# TIDA-01576_ADS8686S_ISO_Interface_Pg3-Po.net
KiCad netlist of a schematic drawn in Altium Designer
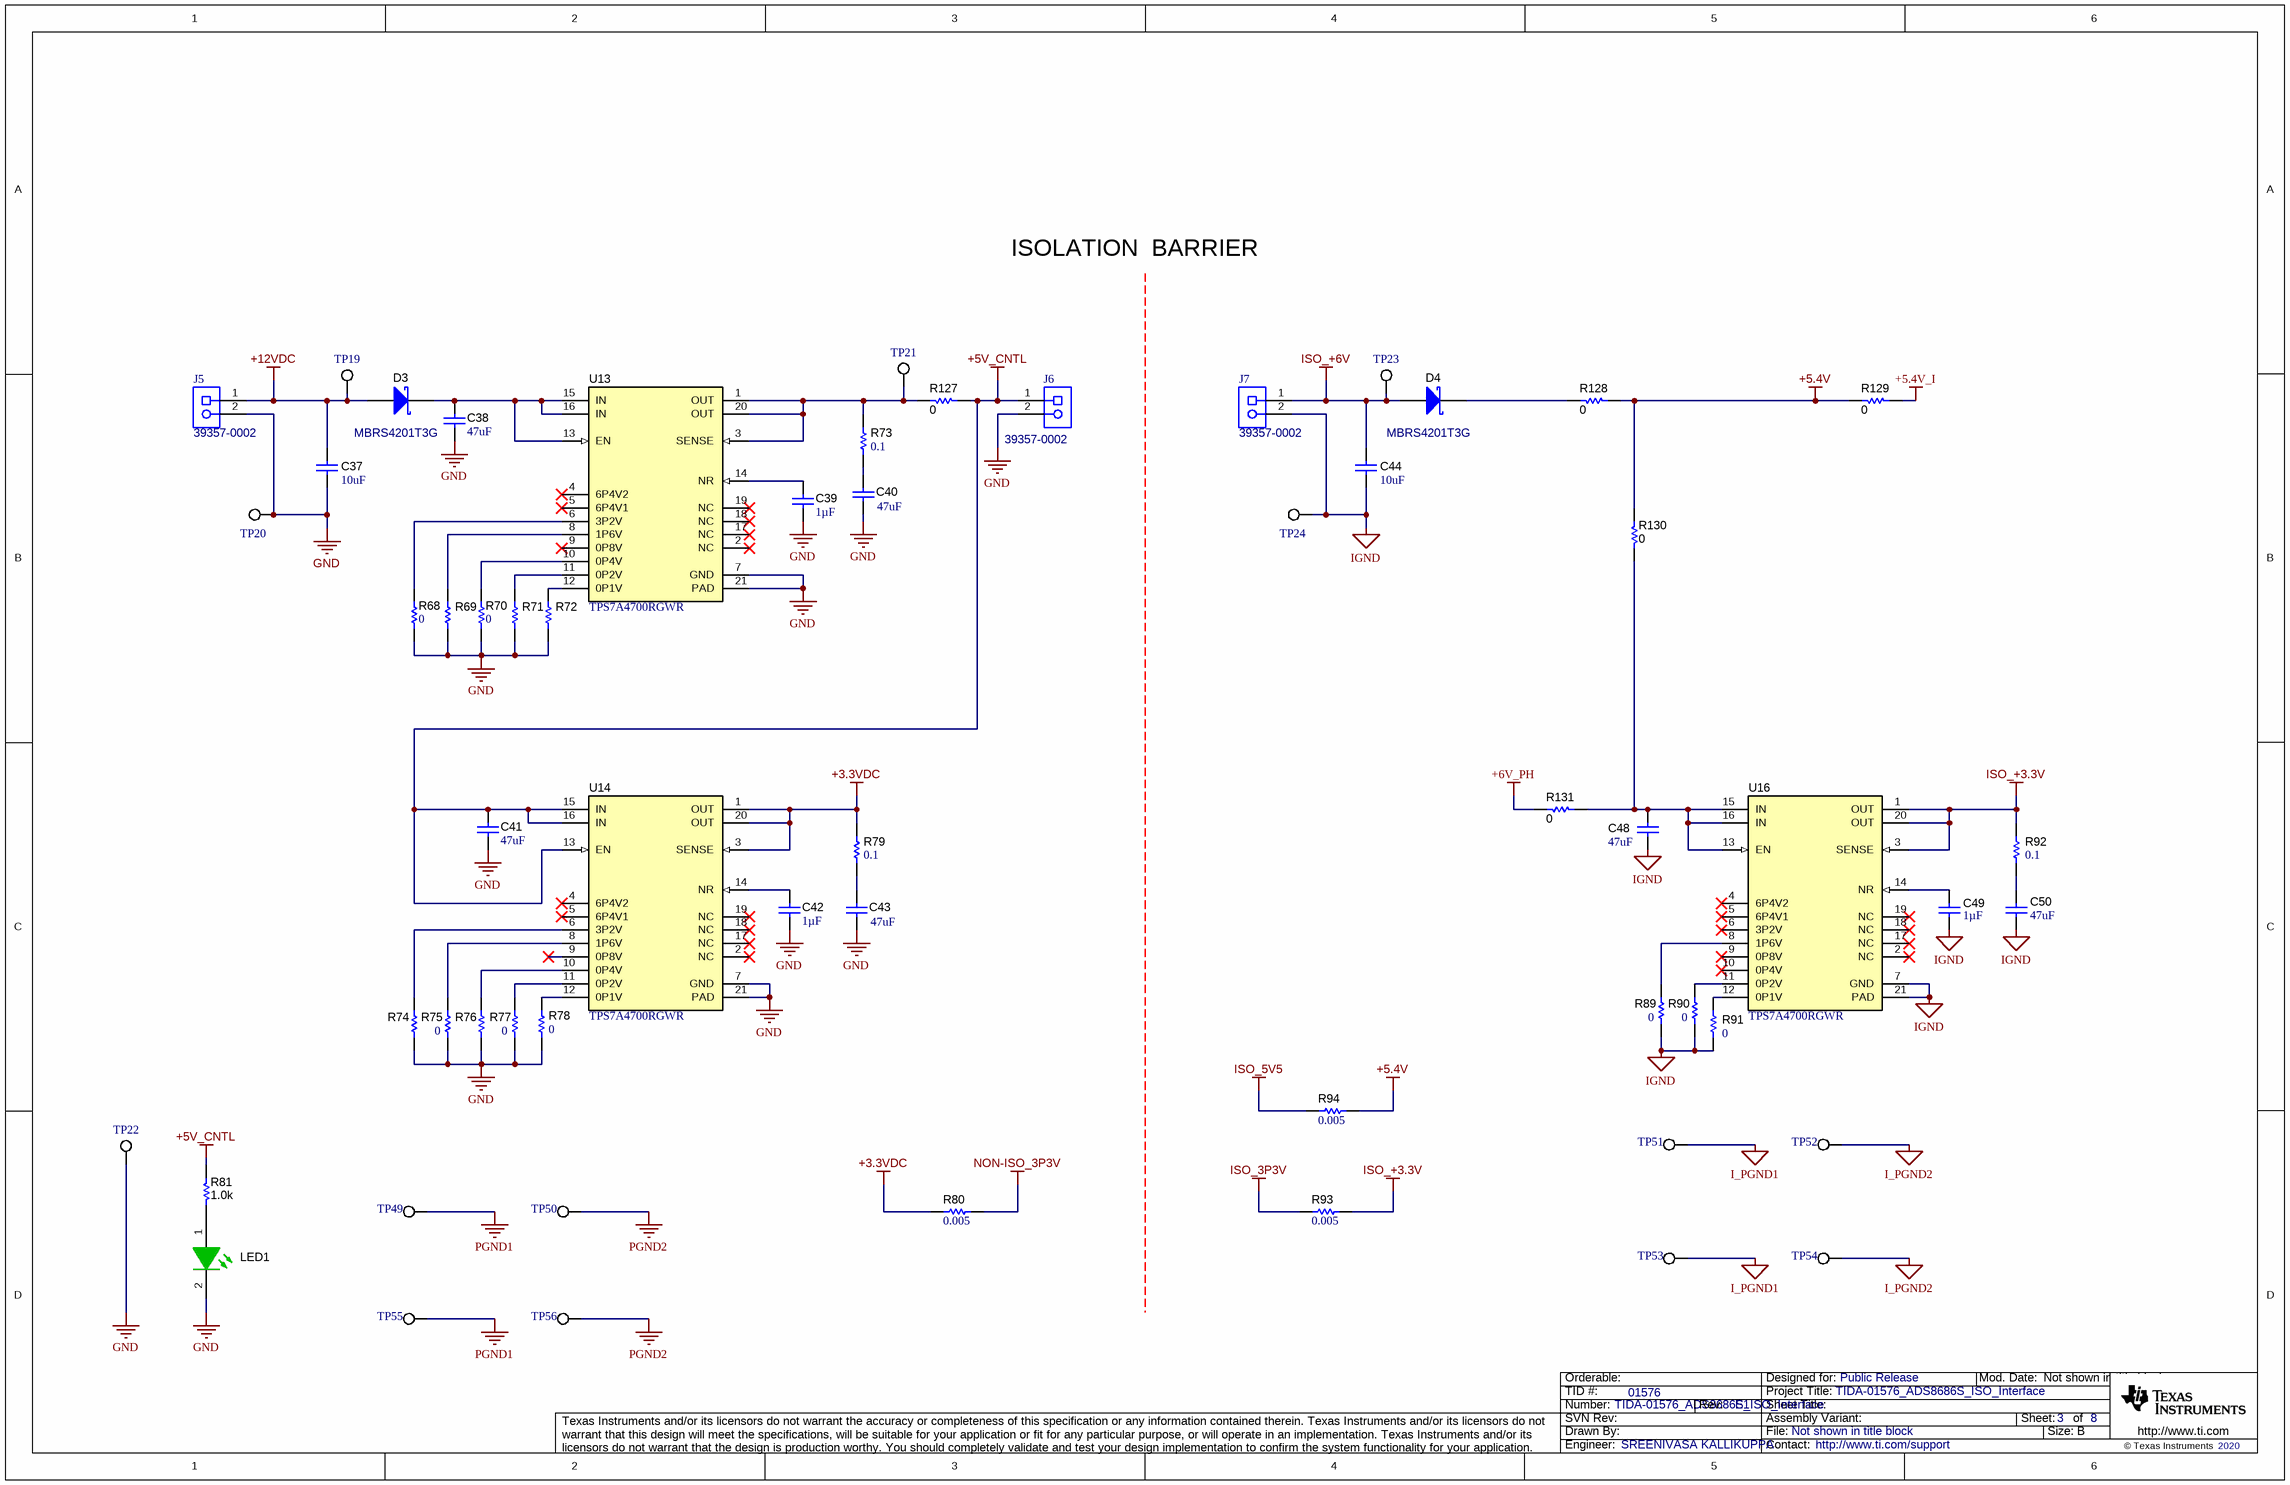
[diagram p0: TIDA-01576_ADS8686S_ISO_Interface_Pg3-PowerSupply.SchDoc]

(export (version "E")
  (design (tool "Eeschema 10.0.6"))
  (components
    (comp (ref "C37")
      (value "GRM32ER71H106KA12L")
      (footprint "1210_270")
      (description "CAP, CERM, 10 uF, 50 V, +/- 10%, X7R, 1210")
      (fields (field (name "MANUFACTURER") "MuRata") (field (name "VALUEDISPLAYED") "10uF"))
      (libsource (lib "Altium Vault - TI") (part "Capacitor"))
    )
    (comp (ref "C38")
      (value "C3216X5R1E476M160AC")
      (footprint "1206_190")
      (description "CAP, CERM, 47 uF, 25 V, +/- 20%, X5R, 1206_190")
      (fields
        (field (name "MANUFACTURER") "TDK")
        (field (name "VALUEDISPLAYED") "47uF")
        (field (name "PUBLISHER") "Texas Instruments")
      )
      (libsource (lib "Altium Vault - TI") (part "Capacitor"))
    )
    (comp (ref "C39")
      (value "C1608X7R1C105K080AC")
      (footprint "0603")
      (description "CAP, CERM, 1 uF, 16 V, +/- 10%, X7R, 0603")
      (fields
        (field (name "MANUFACTURER") "TDK")
        (field (name "CAP_F") "1µF")
        (field (name "PUBLISHER") "Texas Instruments")
      )
      (libsource (lib "Altium Vault - TI") (part "Capacitor"))
    )
    (comp (ref "C40")
      (value "C2012X5R1A476M125AC")
      (footprint "0805_HV")
      (description "CAP, CERM, 47 uF, 10 V, +/- 20%, X5R, 0805")
      (fields
        (field (name "MANUFACTURER") "TDK")
        (field (name "VALUEDISPLAYED") "47uF")
        (field (name "PUBLISHER") "Texas Instruments")
      )
      (libsource (lib "Altium Vault - TI") (part "Capacitor"))
    )
    (comp (ref "C41")
      (value "C3216X5R1E476M160AC")
      (footprint "1206_190")
      (description "CAP, CERM, 47 uF, 25 V, +/- 20%, X5R, 1206_190")
      (fields
        (field (name "MANUFACTURER") "TDK")
        (field (name "VALUEDISPLAYED") "47uF")
        (field (name "PUBLISHER") "Texas Instruments")
      )
      (libsource (lib "Altium Vault - TI") (part "Capacitor"))
    )
    (comp (ref "C42")
      (value "C1608X7R1C105K080AC")
      (footprint "0603")
      (description "CAP, CERM, 1 uF, 16 V, +/- 10%, X7R, 0603")
      (fields
        (field (name "MANUFACTURER") "TDK")
        (field (name "CAP_F") "1µF")
        (field (name "PUBLISHER") "Texas Instruments")
      )
      (libsource (lib "Altium Vault - TI") (part "Capacitor"))
    )
    (comp (ref "C43")
      (value "C2012X5R1A476M125AC")
      (footprint "0805_HV")
      (description "CAP, CERM, 47 uF, 10 V, +/- 20%, X5R, 0805")
      (fields
        (field (name "MANUFACTURER") "TDK")
        (field (name "VALUEDISPLAYED") "47uF")
        (field (name "PUBLISHER") "Texas Instruments")
      )
      (libsource (lib "Altium Vault - TI") (part "Capacitor"))
    )
    (comp (ref "C44")
      (value "GRM32ER71H106KA12L")
      (footprint "1210_270")
      (description "CAP, CERM, 10 uF, 50 V, +/- 10%, X7R, 1210")
      (fields (field (name "MANUFACTURER") "MuRata") (field (name "VALUEDISPLAYED") "10uF"))
      (libsource (lib "Altium Vault - TI") (part "Capacitor"))
    )
    (comp (ref "C48")
      (value "C3216X5R1E476M160AC")
      (footprint "1206_190")
      (description "CAP, CERM, 47 uF, 25 V, +/- 20%, X5R, 1206_190")
      (fields
        (field (name "MANUFACTURER") "TDK")
        (field (name "VALUEDISPLAYED") "47uF")
        (field (name "PUBLISHER") "Texas Instruments")
      )
      (libsource (lib "Altium Vault - TI") (part "Capacitor"))
    )
    (comp (ref "C49")
      (value "C1608X7R1C105K080AC")
      (footprint "0603")
      (description "CAP, CERM, 1 uF, 16 V, +/- 10%, X7R, 0603")
      (fields
        (field (name "MANUFACTURER") "TDK")
        (field (name "CAP_F") "1µF")
        (field (name "PUBLISHER") "Texas Instruments")
      )
      (libsource (lib "Altium Vault - TI") (part "Capacitor"))
    )
    (comp (ref "C50")
      (value "C2012X5R1A476M125AC")
      (footprint "0805_HV")
      (description "CAP, CERM, 47 uF, 10 V, +/- 20%, X5R, 0805")
      (fields
        (field (name "MANUFACTURER") "TDK")
        (field (name "VALUEDISPLAYED") "47uF")
        (field (name "PUBLISHER") "Texas Instruments")
      )
      (libsource (lib "Altium Vault - TI") (part "Capacitor"))
    )
    (comp (ref "D3")
      (value "MBRS4201T3G")
      (footprint "SMC")
      (description "Diode, Schottky, 200 V, 4 A, SMC")
      (fields (field (name "MANUFACTURER") "ON Semiconductor") (field (name "PUBLISHER") "Texas Instruments"))
      (libsource (lib "Altium Vault - TI") (part "DIODE_SCHOTTKY"))
    )
    (comp (ref "D4")
      (value "MBRS4201T3G")
      (footprint "SMC")
      (description "Diode, Schottky, 200 V, 4 A, SMC")
      (fields (field (name "MANUFACTURER") "ON Semiconductor") (field (name "PUBLISHER") "Texas Instruments"))
      (libsource (lib "Altium Vault - TI") (part "DIODE_SCHOTTKY"))
    )
    (comp (ref "J5")
      (value "39357-0002")
      (footprint "MOLEX_39357-0002")
      (description "Terminal Block, 3.5 mm, 2x1, Tin, TH")
      (fields (field (name "MANUFACTURER") "Molex") (field (name "PUBLISHER") "Texas Instruments"))
      (libsource (lib "Altium Vault - TI") (part "Receptacle_2x1"))
    )
    (comp (ref "J6")
      (value "39357-0002")
      (footprint "MOLEX_39357-0002")
      (description "Terminal Block, 3.5 mm, 2x1, Tin, TH")
      (fields (field (name "MANUFACTURER") "Molex") (field (name "PUBLISHER") "Texas Instruments"))
      (libsource (lib "") (part "Receptacle_2x1_1"))
    )
    (comp (ref "J7")
      (value "39357-0002")
      (footprint "MOLEX_39357-0002")
      (description "Terminal Block, 3.5 mm, 2x1, Tin, TH")
      (fields (field (name "MANUFACTURER") "Molex") (field (name "PUBLISHER") "Texas Instruments"))
      (libsource (lib "Altium Vault - TI") (part "Receptacle_2x1"))
    )
    (comp (ref "LED1")
      (value "LTST-C193TGKT-5A")
      (footprint "LTST-C193_Green_S")
      (description "LED, Green, SMD")
      (fields (field (name "MANUFACTURER") "Lite-On"))
      (libsource (lib "Altium Vault - TI") (part "LED_Green_A1K2"))
    )
    (comp (ref "R68")
      (value "CRCW06030000Z0EA")
      (footprint "0603")
      (description "RES, 0, 5%, 0.1 W, 0603")
      (fields
        (field (name "MANUFACTURER") "Vishay-Dale")
        (field (name "VALUEDISPLAYED") "0")
        (field (name "PUBLISHER") "Texas Instruments")
      )
      (libsource (lib "Altium Vault - TI") (part "Resistor"))
    )
    (comp (ref "R69")
      (value "CRCW06030000Z0EA")
      (footprint "0603")
      (description "RES, 0, 5%, 0.1 W, 0603")
      (fields (field (name "MANUFACTURER") "Vishay-Dale") (field (name "PUBLISHER") "Texas Instruments"))
      (libsource (lib "Altium Vault - TI") (part "Resistor"))
    )
    (comp (ref "R70")
      (value "CRCW06030000Z0EA")
      (footprint "0603")
      (description "RES, 0, 5%, 0.1 W, 0603")
      (fields
        (field (name "MANUFACTURER") "Vishay-Dale")
        (field (name "VALUEDISPLAYED") "0")
        (field (name "PUBLISHER") "Texas Instruments")
      )
      (libsource (lib "Altium Vault - TI") (part "Resistor"))
    )
    (comp (ref "R71")
      (value "CRCW06030000Z0EA")
      (footprint "0603")
      (description "RES, 0, 5%, 0.1 W, 0603")
      (fields (field (name "MANUFACTURER") "Vishay-Dale") (field (name "PUBLISHER") "Texas Instruments"))
      (libsource (lib "Altium Vault - TI") (part "Resistor"))
    )
    (comp (ref "R72")
      (value "CRCW06030000Z0EA")
      (footprint "0603")
      (description "RES, 0, 5%, 0.1 W, 0603")
      (fields (field (name "MANUFACTURER") "Vishay-Dale") (field (name "PUBLISHER") "Texas Instruments"))
      (libsource (lib "Altium Vault - TI") (part "Resistor"))
    )
    (comp (ref "R73")
      (value "ERJ-3RSFR10V")
      (footprint "0603")
      (description "RES, 0.1, 1%, 0.1 W, 0603")
      (fields
        (field (name "MANUFACTURER") "Panasonic")
        (field (name "VALUEDISPLAYED") "0.1")
        (field (name "PUBLISHER") "Texas Instruments")
      )
      (libsource (lib "Altium Vault - TI") (part "Resistor"))
    )
    (comp (ref "R74")
      (value "CRCW06030000Z0EA")
      (footprint "0603")
      (description "RES, 0, 5%, 0.1 W, 0603")
      (fields (field (name "MANUFACTURER") "Vishay-Dale") (field (name "PUBLISHER") "Texas Instruments"))
      (libsource (lib "Altium Vault - TI") (part "Resistor"))
    )
    (comp (ref "R75")
      (value "CRCW06030000Z0EA")
      (footprint "0603")
      (description "RES, 0, 5%, 0.1 W, 0603")
      (fields
        (field (name "MANUFACTURER") "Vishay-Dale")
        (field (name "VALUEDISPLAYED") "0")
        (field (name "PUBLISHER") "Texas Instruments")
      )
      (libsource (lib "Altium Vault - TI") (part "Resistor"))
    )
    (comp (ref "R76")
      (value "CRCW06030000Z0EA")
      (footprint "0603")
      (description "RES, 0, 5%, 0.1 W, 0603")
      (fields (field (name "MANUFACTURER") "Vishay-Dale") (field (name "PUBLISHER") "Texas Instruments"))
      (libsource (lib "Altium Vault - TI") (part "Resistor"))
    )
    (comp (ref "R77")
      (value "CRCW06030000Z0EA")
      (footprint "0603")
      (description "RES, 0, 5%, 0.1 W, 0603")
      (fields
        (field (name "MANUFACTURER") "Vishay-Dale")
        (field (name "VALUEDISPLAYED") "0")
        (field (name "PUBLISHER") "Texas Instruments")
      )
      (libsource (lib "Altium Vault - TI") (part "Resistor"))
    )
    (comp (ref "R78")
      (value "CRCW06030000Z0EA")
      (footprint "0603")
      (description "RES, 0, 5%, 0.1 W, 0603")
      (fields
        (field (name "MANUFACTURER") "Vishay-Dale")
        (field (name "VALUEDISPLAYED") "0")
        (field (name "PUBLISHER") "Texas Instruments")
      )
      (libsource (lib "Altium Vault - TI") (part "Resistor"))
    )
    (comp (ref "R79")
      (value "ERJ-3RSFR10V")
      (footprint "0603")
      (description "RES, 0.1, 1%, 0.1 W, 0603")
      (fields
        (field (name "MANUFACTURER") "Panasonic")
        (field (name "VALUEDISPLAYED") "0.1")
        (field (name "PUBLISHER") "Texas Instruments")
      )
      (libsource (lib "Altium Vault - TI") (part "Resistor"))
    )
    (comp (ref "R80")
      (value "ERJ6LWFR005V")
      (footprint "0805_HV")
      (description "RES, 0.005, 1%, 0.5 W, AEC-Q200 Grade 1, 0805")
      (fields (field (name "MANUFACTURER") "Panasonic") (field (name "VALUEDISPLAYED") "0.005"))
      (libsource (lib "Altium Vault - TI") (part "Resistor"))
    )
    (comp (ref "R81")
      (value "RC0603JR-071KL")
      (footprint "0603")
      (description "RES, 1.0 k, 5%, 0.1 W, 0603")
      (fields
        (field (name "VALUEDISPLAYED") "1.0k")
        (field (name "MANUFACTURER") "Yageo America")
        (field (name "PUBLISHER") "Texas Instruments")
      )
      (libsource (lib "Resistor_0603") (part "RC0603JR-071KL"))
    )
    (comp (ref "R89")
      (value "CRCW06030000Z0EA")
      (footprint "0603")
      (description "RES, 0, 5%, 0.1 W, 0603")
      (fields
        (field (name "MANUFACTURER") "Vishay-Dale")
        (field (name "VALUEDISPLAYED") "0")
        (field (name "PUBLISHER") "Texas Instruments")
      )
      (libsource (lib "Altium Vault - TI") (part "Resistor"))
    )
    (comp (ref "R90")
      (value "CRCW06030000Z0EA")
      (footprint "0603")
      (description "RES, 0, 5%, 0.1 W, 0603")
      (fields
        (field (name "MANUFACTURER") "Vishay-Dale")
        (field (name "VALUEDISPLAYED") "0")
        (field (name "PUBLISHER") "Texas Instruments")
      )
      (libsource (lib "Altium Vault - TI") (part "Resistor"))
    )
    (comp (ref "R91")
      (value "CRCW06030000Z0EA")
      (footprint "0603")
      (description "RES, 0, 5%, 0.1 W, 0603")
      (fields
        (field (name "MANUFACTURER") "Vishay-Dale")
        (field (name "VALUEDISPLAYED") "0")
        (field (name "PUBLISHER") "Texas Instruments")
      )
      (libsource (lib "Altium Vault - TI") (part "Resistor"))
    )
    (comp (ref "R92")
      (value "ERJ-3RSFR10V")
      (footprint "0603")
      (description "RES, 0.1, 1%, 0.1 W, 0603")
      (fields
        (field (name "MANUFACTURER") "Panasonic")
        (field (name "VALUEDISPLAYED") "0.1")
        (field (name "PUBLISHER") "Texas Instruments")
      )
      (libsource (lib "Altium Vault - TI") (part "Resistor"))
    )
    (comp (ref "R93")
      (value "ERJ6LWFR005V")
      (footprint "0805_HV")
      (description "RES, 0.005, 1%, 0.5 W, AEC-Q200 Grade 1, 0805")
      (fields (field (name "MANUFACTURER") "Panasonic") (field (name "VALUEDISPLAYED") "0.005"))
      (libsource (lib "Altium Vault - TI") (part "Resistor"))
    )
    (comp (ref "R94")
      (value "ERJ6LWFR005V")
      (footprint "0805_HV")
      (description "RES, 0.005, 1%, 0.5 W, AEC-Q200 Grade 1, 0805")
      (fields (field (name "MANUFACTURER") "Panasonic") (field (name "VALUEDISPLAYED") "0.005"))
      (libsource (lib "Altium Vault - TI") (part "Resistor"))
    )
    (comp (ref "R127")
      (value "CRCW06030000Z0EA")
      (footprint "0603")
      (description "RES, 0, 5%, 0.1 W, 0603")
      (fields
        (field (name "VALUEDISPLAYED") "0")
        (field (name "MANUFACTURER") "Vishay-Dale")
        (field (name "PUBLISHER") "Texas Instruments")
      )
      (libsource (lib "Resistor_0603") (part "CRCW06030000Z0EA"))
    )
    (comp (ref "R128")
      (value "CRCW06030000Z0EA")
      (footprint "0603")
      (description "RES, 0, 5%, 0.1 W, 0603")
      (fields
        (field (name "VALUEDISPLAYED") "0")
        (field (name "MANUFACTURER") "Vishay-Dale")
        (field (name "PUBLISHER") "Texas Instruments")
      )
      (libsource (lib "Resistor_0603") (part "CRCW06030000Z0EA"))
    )
    (comp (ref "R129")
      (value "CRCW06030000Z0EA")
      (footprint "0603")
      (description "RES, 0, 5%, 0.1 W, 0603")
      (fields
        (field (name "VALUEDISPLAYED") "0")
        (field (name "MANUFACTURER") "Vishay-Dale")
        (field (name "PUBLISHER") "Texas Instruments")
      )
      (libsource (lib "Resistor_0603") (part "CRCW06030000Z0EA"))
    )
    (comp (ref "R130")
      (value "CRCW06030000Z0EA")
      (footprint "0603")
      (description "RES, 0, 5%, 0.1 W, 0603")
      (fields
        (field (name "VALUEDISPLAYED") "0")
        (field (name "MANUFACTURER") "Vishay-Dale")
        (field (name "PUBLISHER") "Texas Instruments")
      )
      (libsource (lib "Resistor_0603") (part "CRCW06030000Z0EA"))
    )
    (comp (ref "R131")
      (value "CRCW06030000Z0EA")
      (footprint "0603")
      (description "RES, 0, 5%, 0.1 W, 0603")
      (fields
        (field (name "VALUEDISPLAYED") "0")
        (field (name "MANUFACTURER") "Vishay-Dale")
        (field (name "PUBLISHER") "Texas Instruments")
      )
      (libsource (lib "Resistor_0603") (part "CRCW06030000Z0EA"))
    )
    (comp (ref "TP19")
      (value "5015")
      (footprint "Testpoint_Keystone_Miniature")
      (description "Test Point, Miniature, SMT")
      (fields (field (name "MANUFACTURER") "Keystone") (field (name "PUBLISHER") "Texas Instruments"))
      (libsource (lib "Altium Vault - TI") (part "5015"))
    )
    (comp (ref "TP20")
      (value "5015")
      (footprint "Testpoint_Keystone_Miniature")
      (description "Test Point, Miniature, SMT")
      (fields (field (name "MANUFACTURER") "Keystone") (field (name "PUBLISHER") "Texas Instruments"))
      (libsource (lib "Altium Vault - TI") (part "5015"))
    )
    (comp (ref "TP21")
      (value "5015")
      (footprint "Testpoint_Keystone_Miniature")
      (description "Test Point, Miniature, SMT")
      (fields (field (name "MANUFACTURER") "Keystone") (field (name "PUBLISHER") "Texas Instruments"))
      (libsource (lib "Altium Vault - TI") (part "5015"))
    )
    (comp (ref "TP22")
      (value "5015")
      (footprint "Testpoint_Keystone_Miniature")
      (description "Test Point, Miniature, SMT")
      (fields (field (name "MANUFACTURER") "Keystone") (field (name "PUBLISHER") "Texas Instruments"))
      (libsource (lib "Altium Vault - TI") (part "5015"))
    )
    (comp (ref "TP23")
      (value "5015")
      (footprint "Testpoint_Keystone_Miniature")
      (description "Test Point, Miniature, SMT")
      (fields (field (name "MANUFACTURER") "Keystone") (field (name "PUBLISHER") "Texas Instruments"))
      (libsource (lib "Altium Vault - TI") (part "5015"))
    )
    (comp (ref "TP24")
      (value "5015")
      (footprint "Testpoint_Keystone_Miniature")
      (description "Test Point, Miniature, SMT")
      (fields (field (name "MANUFACTURER") "Keystone") (field (name "PUBLISHER") "Texas Instruments"))
      (libsource (lib "Altium Vault - TI") (part "5015"))
    )
    (comp (ref "TP49")
      (value "5015")
      (footprint "Testpoint_Keystone_Miniature")
      (description "Test Point, Miniature, SMT")
      (fields (field (name "MANUFACTURER") "Keystone") (field (name "PUBLISHER") "Texas Instruments"))
      (libsource (lib "Altium Vault - TI") (part "5015"))
    )
    (comp (ref "TP50")
      (value "5015")
      (footprint "Testpoint_Keystone_Miniature")
      (description "Test Point, Miniature, SMT")
      (fields (field (name "MANUFACTURER") "Keystone") (field (name "PUBLISHER") "Texas Instruments"))
      (libsource (lib "Altium Vault - TI") (part "5015"))
    )
    (comp (ref "TP51")
      (value "5015")
      (footprint "Testpoint_Keystone_Miniature")
      (description "Test Point, Miniature, SMT")
      (fields (field (name "MANUFACTURER") "Keystone") (field (name "PUBLISHER") "Texas Instruments"))
      (libsource (lib "Altium Vault - TI") (part "5015"))
    )
    (comp (ref "TP52")
      (value "5015")
      (footprint "Testpoint_Keystone_Miniature")
      (description "Test Point, Miniature, SMT")
      (fields (field (name "MANUFACTURER") "Keystone") (field (name "PUBLISHER") "Texas Instruments"))
      (libsource (lib "Altium Vault - TI") (part "5015"))
    )
    (comp (ref "TP53")
      (value "5015")
      (footprint "Testpoint_Keystone_Miniature")
      (description "Test Point, Miniature, SMT")
      (fields (field (name "MANUFACTURER") "Keystone") (field (name "PUBLISHER") "Texas Instruments"))
      (libsource (lib "Altium Vault - TI") (part "5015"))
    )
    (comp (ref "TP54")
      (value "5015")
      (footprint "Testpoint_Keystone_Miniature")
      (description "Test Point, Miniature, SMT")
      (fields (field (name "MANUFACTURER") "Keystone") (field (name "PUBLISHER") "Texas Instruments"))
      (libsource (lib "Altium Vault - TI") (part "5015"))
    )
    (comp (ref "TP55")
      (value "5015")
      (footprint "Testpoint_Keystone_Miniature")
      (description "Test Point, Miniature, SMT")
      (fields (field (name "MANUFACTURER") "Keystone") (field (name "PUBLISHER") "Texas Instruments"))
      (libsource (lib "Altium Vault - TI") (part "5015"))
    )
    (comp (ref "TP56")
      (value "5015")
      (footprint "Testpoint_Keystone_Miniature")
      (description "Test Point, Miniature, SMT")
      (fields (field (name "MANUFACTURER") "Keystone") (field (name "PUBLISHER") "Texas Instruments"))
      (libsource (lib "Altium Vault - TI") (part "5015"))
    )
    (comp (ref "U13")
      (value "TPS7A4700RGWR")
      (footprint "RGW0020A")
      (description "36-V, 1-A, 4.17-uVRMS, RF LDO Voltage Regulator, RGW0020A (VQFN-20)")
      (fields
        (field (name "ALTERNATE PARTNUMBER") "TPS7A4700RGWT")
        (field (name "MANUFACTURER") "Texas Instruments")
        (field (name "PARTNUMBER") "TPS7A4700RGWR")
        (field (name "PUBLISHER") "Texas Instruments")
      )
      (libsource (lib "Altium Vault - TI") (part "TPS7A4700RGW"))
    )
    (comp (ref "U14")
      (value "TPS7A4700RGWR")
      (footprint "RGW0020A")
      (description "36-V, 1-A, 4.17-uVRMS, RF LDO Voltage Regulator, RGW0020A (VQFN-20)")
      (fields
        (field (name "ALTERNATE PARTNUMBER") "TPS7A4700RGWT")
        (field (name "MANUFACTURER") "Texas Instruments")
        (field (name "PARTNUMBER") "TPS7A4700RGWR")
        (field (name "PUBLISHER") "Texas Instruments")
      )
      (libsource (lib "Altium Vault - TI") (part "TPS7A4700RGW"))
    )
    (comp (ref "U16")
      (value "TPS7A4700RGWR")
      (footprint "RGW0020A")
      (description "36-V, 1-A, 4.17-uVRMS, RF LDO Voltage Regulator, RGW0020A (VQFN-20)")
      (fields
        (field (name "ALTERNATE PARTNUMBER") "TPS7A4700RGWT")
        (field (name "MANUFACTURER") "Texas Instruments")
        (field (name "PARTNUMBER") "TPS7A4700RGWR")
        (field (name "PUBLISHER") "Texas Instruments")
      )
      (libsource (lib "Altium Vault - TI") (part "TPS7A4700RGW"))
    )
  )
  (nets
    (net (code "1") (name "+3.3VDC") (class "Default")
      (node (ref "R79") (pin "2") (pinfunction "2_2") (pintype "passive"))
      (node (ref "R80") (pin "2") (pinfunction "2_2") (pintype "passive"))
      (node (ref "U14") (pin "1") (pinfunction "OUT_1") (pintype "power_in"))
      (node (ref "U14") (pin "20") (pinfunction "OUT_20") (pintype "power_in"))
      (node (ref "U14") (pin "3") (pinfunction "SENSE_3") (pintype "input"))
    )
    (net (code "2") (name "+5.4V") (class "Default")
      (node (ref "R128") (pin "1") (pinfunction "1_1") (pintype "passive"))
      (node (ref "R129") (pin "2") (pinfunction "2_2") (pintype "passive"))
      (node (ref "R130") (pin "1") (pinfunction "1_1") (pintype "passive"))
      (node (ref "R94") (pin "2") (pinfunction "2_2") (pintype "passive"))
    )
    (net (code "3") (name "+5.4V_I") (class "Default")
      (node (ref "R129") (pin "1") (pinfunction "1_1") (pintype "passive"))
    )
    (net (code "4") (name "+5V_CNTL") (class "Default")
      (node (ref "C41") (pin "1") (pinfunction "1_1") (pintype "passive"))
      (node (ref "J6") (pin "1") (pinfunction "1_1") (pintype "passive"))
      (node (ref "R127") (pin "1") (pinfunction "1_1") (pintype "passive"))
      (node (ref "R81") (pin "2") (pinfunction "2_2") (pintype "passive"))
      (node (ref "U14") (pin "13") (pinfunction "EN_13") (pintype "input"))
      (node (ref "U14") (pin "15") (pinfunction "IN_15") (pintype "power_in"))
      (node (ref "U14") (pin "16") (pinfunction "IN_16") (pintype "power_in"))
    )
    (net (code "5") (name "+6V_PH") (class "Default")
      (node (ref "R131") (pin "1") (pinfunction "1_1") (pintype "passive"))
    )
    (net (code "6") (name "+12VDC") (class "Default")
      (node (ref "C37") (pin "1") (pinfunction "1_1") (pintype "passive"))
      (node (ref "D3") (pin "2") (pinfunction "A_2") (pintype "passive"))
      (node (ref "J5") (pin "1") (pinfunction "1_1") (pintype "passive"))
      (node (ref "TP19") (pin "1") (pintype "passive"))
    )
    (net (code "7") (name "GND") (class "Default")
      (node (ref "C37") (pin "2") (pinfunction "2_2") (pintype "passive"))
      (node (ref "C38") (pin "2") (pinfunction "2_2") (pintype "passive"))
      (node (ref "C39") (pin "2") (pinfunction "2_2") (pintype "passive"))
      (node (ref "C40") (pin "2") (pinfunction "2_2") (pintype "passive"))
      (node (ref "C41") (pin "2") (pinfunction "2_2") (pintype "passive"))
      (node (ref "C42") (pin "2") (pinfunction "2_2") (pintype "passive"))
      (node (ref "C43") (pin "2") (pinfunction "2_2") (pintype "passive"))
      (node (ref "J5") (pin "2") (pinfunction "2_2") (pintype "passive"))
      (node (ref "J6") (pin "2") (pinfunction "2_2") (pintype "passive"))
      (node (ref "LED1") (pin "2") (pinfunction "K_2") (pintype "passive"))
      (node (ref "R68") (pin "1") (pinfunction "1_1") (pintype "passive"))
      (node (ref "R69") (pin "1") (pinfunction "1_1") (pintype "passive"))
      (node (ref "R70") (pin "1") (pinfunction "1_1") (pintype "passive"))
      (node (ref "R71") (pin "1") (pinfunction "1_1") (pintype "passive"))
      (node (ref "R72") (pin "1") (pinfunction "1_1") (pintype "passive"))
      (node (ref "R74") (pin "1") (pinfunction "1_1") (pintype "passive"))
      (node (ref "R75") (pin "1") (pinfunction "1_1") (pintype "passive"))
      (node (ref "R76") (pin "1") (pinfunction "1_1") (pintype "passive"))
      (node (ref "R77") (pin "1") (pinfunction "1_1") (pintype "passive"))
      (node (ref "R78") (pin "1") (pinfunction "1_1") (pintype "passive"))
      (node (ref "TP20") (pin "1") (pintype "passive"))
      (node (ref "TP22") (pin "1") (pintype "passive"))
      (node (ref "U13") (pin "21") (pinfunction "PAD_21") (pintype "passive"))
      (node (ref "U13") (pin "7") (pinfunction "GND_7") (pintype "power_in"))
      (node (ref "U14") (pin "21") (pinfunction "PAD_21") (pintype "passive"))
      (node (ref "U14") (pin "7") (pinfunction "GND_7") (pintype "power_in"))
    )
    (net (code "8") (name "IGND") (class "Default")
      (node (ref "C44") (pin "2") (pinfunction "2_2") (pintype "passive"))
      (node (ref "C48") (pin "2") (pinfunction "2_2") (pintype "passive"))
      (node (ref "C49") (pin "2") (pinfunction "2_2") (pintype "passive"))
      (node (ref "C50") (pin "2") (pinfunction "2_2") (pintype "passive"))
      (node (ref "J7") (pin "2") (pinfunction "2_2") (pintype "passive"))
      (node (ref "R89") (pin "1") (pinfunction "1_1") (pintype "passive"))
      (node (ref "R90") (pin "1") (pinfunction "1_1") (pintype "passive"))
      (node (ref "R91") (pin "1") (pinfunction "1_1") (pintype "passive"))
      (node (ref "TP24") (pin "1") (pintype "passive"))
      (node (ref "U16") (pin "21") (pinfunction "PAD_21") (pintype "passive"))
      (node (ref "U16") (pin "7") (pinfunction "GND_7") (pintype "power_in"))
    )
    (net (code "9") (name "ISO_+3.3V") (class "Default")
      (node (ref "R92") (pin "2") (pinfunction "2_2") (pintype "passive"))
      (node (ref "R93") (pin "2") (pinfunction "2_2") (pintype "passive"))
      (node (ref "U16") (pin "1") (pinfunction "OUT_1") (pintype "power_in"))
      (node (ref "U16") (pin "20") (pinfunction "OUT_20") (pintype "power_in"))
      (node (ref "U16") (pin "3") (pinfunction "SENSE_3") (pintype "input"))
    )
    (net (code "10") (name "ISO_+6V") (class "Default")
      (node (ref "C44") (pin "1") (pinfunction "1_1") (pintype "passive"))
      (node (ref "D4") (pin "2") (pinfunction "A_2") (pintype "passive"))
      (node (ref "J7") (pin "1") (pinfunction "1_1") (pintype "passive"))
      (node (ref "TP23") (pin "1") (pintype "passive"))
    )
    (net (code "11") (name "ISO_3P3V") (class "Default")
      (node (ref "R93") (pin "1") (pinfunction "1_1") (pintype "passive"))
    )
    (net (code "12") (name "ISO_5V5") (class "Default")
      (node (ref "R94") (pin "1") (pinfunction "1_1") (pintype "passive"))
    )
    (net (code "13") (name "I_PGND1") (class "Default")
      (node (ref "TP51") (pin "1") (pintype "passive"))
      (node (ref "TP53") (pin "1") (pintype "passive"))
    )
    (net (code "14") (name "I_PGND2") (class "Default")
      (node (ref "TP52") (pin "1") (pintype "passive"))
      (node (ref "TP54") (pin "1") (pintype "passive"))
    )
    (net (code "15") (name "NON-ISO_3P3V") (class "Default")
      (node (ref "R80") (pin "1") (pinfunction "1_1") (pintype "passive"))
    )
    (net (code "16") (name "Net-(C40-Pad1)") (class "Default")
      (node (ref "C40") (pin "1") (pinfunction "1_1") (pintype "passive"))
      (node (ref "R73") (pin "1") (pinfunction "1_1") (pintype "passive"))
    )
    (net (code "17") (name "Net-(C43-Pad1)") (class "Default")
      (node (ref "C43") (pin "1") (pinfunction "1_1") (pintype "passive"))
      (node (ref "R79") (pin "1") (pinfunction "1_1") (pintype "passive"))
    )
    (net (code "18") (name "Net-(C50-Pad1)") (class "Default")
      (node (ref "C50") (pin "1") (pinfunction "1_1") (pintype "passive"))
      (node (ref "R92") (pin "1") (pinfunction "1_1") (pintype "passive"))
    )
    (net (code "19") (name "Net-(D3-K)") (class "Default")
      (node (ref "C38") (pin "1") (pinfunction "1_1") (pintype "passive"))
      (node (ref "D3") (pin "1") (pinfunction "K_1") (pintype "passive"))
      (node (ref "U13") (pin "13") (pinfunction "EN_13") (pintype "input"))
      (node (ref "U13") (pin "15") (pinfunction "IN_15") (pintype "power_in"))
      (node (ref "U13") (pin "16") (pinfunction "IN_16") (pintype "power_in"))
    )
    (net (code "20") (name "Net-(D4-K)") (class "Default")
      (node (ref "D4") (pin "1") (pinfunction "K_1") (pintype "passive"))
      (node (ref "R128") (pin "2") (pinfunction "2_2") (pintype "passive"))
    )
    (net (code "21") (name "Net-(LED1-A)") (class "Default")
      (node (ref "LED1") (pin "1") (pinfunction "A_1") (pintype "passive"))
      (node (ref "R81") (pin "1") (pinfunction "1_1") (pintype "passive"))
    )
    (net (code "22") (name "Net-(U13-0P1V)") (class "Default")
      (node (ref "R72") (pin "2") (pinfunction "2_2") (pintype "passive"))
      (node (ref "U13") (pin "12") (pinfunction "0P1V_12") (pintype "passive"))
    )
    (net (code "23") (name "Net-(U13-0P2V)") (class "Default")
      (node (ref "R71") (pin "2") (pinfunction "2_2") (pintype "passive"))
      (node (ref "U13") (pin "11") (pinfunction "0P2V_11") (pintype "passive"))
    )
    (net (code "24") (name "Net-(U13-0P4V)") (class "Default")
      (node (ref "R70") (pin "2") (pinfunction "2_2") (pintype "passive"))
      (node (ref "U13") (pin "10") (pinfunction "0P4V_10") (pintype "passive"))
    )
    (net (code "25") (name "Net-(U13-1P6V)") (class "Default")
      (node (ref "R69") (pin "2") (pinfunction "2_2") (pintype "passive"))
      (node (ref "U13") (pin "8") (pinfunction "1P6V_8") (pintype "passive"))
    )
    (net (code "26") (name "Net-(U13-3P2V)") (class "Default")
      (node (ref "R68") (pin "2") (pinfunction "2_2") (pintype "passive"))
      (node (ref "U13") (pin "6") (pinfunction "3P2V_6") (pintype "passive"))
    )
    (net (code "27") (name "Net-(U13-NR)") (class "Default")
      (node (ref "C39") (pin "1") (pinfunction "1_1") (pintype "passive"))
      (node (ref "U13") (pin "14") (pinfunction "NR_14") (pintype "input"))
    )
    (net (code "28") (name "Net-(U13-SENSE)") (class "Default")
      (node (ref "R127") (pin "2") (pinfunction "2_2") (pintype "passive"))
      (node (ref "R73") (pin "2") (pinfunction "2_2") (pintype "passive"))
      (node (ref "TP21") (pin "1") (pintype "passive"))
      (node (ref "U13") (pin "1") (pinfunction "OUT_1") (pintype "power_in"))
      (node (ref "U13") (pin "20") (pinfunction "OUT_20") (pintype "power_in"))
      (node (ref "U13") (pin "3") (pinfunction "SENSE_3") (pintype "input"))
    )
    (net (code "29") (name "Net-(U14-0P1V)") (class "Default")
      (node (ref "R78") (pin "2") (pinfunction "2_2") (pintype "passive"))
      (node (ref "U14") (pin "12") (pinfunction "0P1V_12") (pintype "passive"))
    )
    (net (code "30") (name "Net-(U14-0P2V)") (class "Default")
      (node (ref "R77") (pin "2") (pinfunction "2_2") (pintype "passive"))
      (node (ref "U14") (pin "11") (pinfunction "0P2V_11") (pintype "passive"))
    )
    (net (code "31") (name "Net-(U14-0P4V)") (class "Default")
      (node (ref "R76") (pin "2") (pinfunction "2_2") (pintype "passive"))
      (node (ref "U14") (pin "10") (pinfunction "0P4V_10") (pintype "passive"))
    )
    (net (code "32") (name "Net-(U14-1P6V)") (class "Default")
      (node (ref "R75") (pin "2") (pinfunction "2_2") (pintype "passive"))
      (node (ref "U14") (pin "8") (pinfunction "1P6V_8") (pintype "passive"))
    )
    (net (code "33") (name "Net-(U14-3P2V)") (class "Default")
      (node (ref "R74") (pin "2") (pinfunction "2_2") (pintype "passive"))
      (node (ref "U14") (pin "6") (pinfunction "3P2V_6") (pintype "passive"))
    )
    (net (code "34") (name "Net-(U14-NR)") (class "Default")
      (node (ref "C42") (pin "1") (pinfunction "1_1") (pintype "passive"))
      (node (ref "U14") (pin "14") (pinfunction "NR_14") (pintype "input"))
    )
    (net (code "35") (name "Net-(U16-0P1V)") (class "Default")
      (node (ref "R91") (pin "2") (pinfunction "2_2") (pintype "passive"))
      (node (ref "U16") (pin "12") (pinfunction "0P1V_12") (pintype "passive"))
    )
    (net (code "36") (name "Net-(U16-0P2V)") (class "Default")
      (node (ref "R90") (pin "2") (pinfunction "2_2") (pintype "passive"))
      (node (ref "U16") (pin "11") (pinfunction "0P2V_11") (pintype "passive"))
    )
    (net (code "37") (name "Net-(U16-1P6V)") (class "Default")
      (node (ref "R89") (pin "2") (pinfunction "2_2") (pintype "passive"))
      (node (ref "U16") (pin "8") (pinfunction "1P6V_8") (pintype "passive"))
    )
    (net (code "38") (name "Net-(U16-EN)") (class "Default")
      (node (ref "C48") (pin "1") (pinfunction "1_1") (pintype "passive"))
      (node (ref "R130") (pin "2") (pinfunction "2_2") (pintype "passive"))
      (node (ref "R131") (pin "2") (pinfunction "2_2") (pintype "passive"))
      (node (ref "U16") (pin "13") (pinfunction "EN_13") (pintype "input"))
      (node (ref "U16") (pin "15") (pinfunction "IN_15") (pintype "power_in"))
      (node (ref "U16") (pin "16") (pinfunction "IN_16") (pintype "power_in"))
    )
    (net (code "39") (name "Net-(U16-NR)") (class "Default")
      (node (ref "C49") (pin "1") (pinfunction "1_1") (pintype "passive"))
      (node (ref "U16") (pin "14") (pinfunction "NR_14") (pintype "input"))
    )
    (net (code "40") (name "PGND1") (class "Default")
      (node (ref "TP49") (pin "1") (pintype "passive"))
      (node (ref "TP55") (pin "1") (pintype "passive"))
    )
    (net (code "41") (name "PGND2") (class "Default")
      (node (ref "TP50") (pin "1") (pintype "passive"))
      (node (ref "TP56") (pin "1") (pintype "passive"))
    )
    (net (code "42") (name "unconnected-(U13-0P8V-Pad9)") (class "Default")
      (node (ref "U13") (pin "9") (pinfunction "0P8V_9") (pintype "passive+no_connect"))
    )
    (net (code "43") (name "unconnected-(U13-6P4V1-Pad5)") (class "Default")
      (node (ref "U13") (pin "5") (pinfunction "6P4V1_5") (pintype "passive+no_connect"))
    )
    (net (code "44") (name "unconnected-(U13-6P4V2-Pad4)") (class "Default")
      (node (ref "U13") (pin "4") (pinfunction "6P4V2_4") (pintype "passive+no_connect"))
    )
    (net (code "45") (name "unconnected-(U13-NC-Pad2)") (class "Default")
      (node (ref "U13") (pin "2") (pinfunction "NC_2") (pintype "passive+no_connect"))
    )
    (net (code "46") (name "unconnected-(U13-NC-Pad17)") (class "Default")
      (node (ref "U13") (pin "17") (pinfunction "NC_17") (pintype "passive+no_connect"))
    )
    (net (code "47") (name "unconnected-(U13-NC-Pad18)") (class "Default")
      (node (ref "U13") (pin "18") (pinfunction "NC_18") (pintype "passive+no_connect"))
    )
    (net (code "48") (name "unconnected-(U13-NC-Pad19)") (class "Default")
      (node (ref "U13") (pin "19") (pinfunction "NC_19") (pintype "passive+no_connect"))
    )
    (net (code "49") (name "unconnected-(U14-0P8V-Pad9)") (class "Default")
      (node (ref "U14") (pin "9") (pinfunction "0P8V_9") (pintype "passive+no_connect"))
    )
    (net (code "50") (name "unconnected-(U14-6P4V1-Pad5)") (class "Default")
      (node (ref "U14") (pin "5") (pinfunction "6P4V1_5") (pintype "passive+no_connect"))
    )
    (net (code "51") (name "unconnected-(U14-6P4V2-Pad4)") (class "Default")
      (node (ref "U14") (pin "4") (pinfunction "6P4V2_4") (pintype "passive+no_connect"))
    )
    (net (code "52") (name "unconnected-(U14-NC-Pad2)") (class "Default")
      (node (ref "U14") (pin "2") (pinfunction "NC_2") (pintype "passive+no_connect"))
    )
    (net (code "53") (name "unconnected-(U14-NC-Pad17)") (class "Default")
      (node (ref "U14") (pin "17") (pinfunction "NC_17") (pintype "passive+no_connect"))
    )
    (net (code "54") (name "unconnected-(U14-NC-Pad18)") (class "Default")
      (node (ref "U14") (pin "18") (pinfunction "NC_18") (pintype "passive+no_connect"))
    )
    (net (code "55") (name "unconnected-(U14-NC-Pad19)") (class "Default")
      (node (ref "U14") (pin "19") (pinfunction "NC_19") (pintype "passive+no_connect"))
    )
    (net (code "56") (name "unconnected-(U16-0P4V-Pad10)") (class "Default")
      (node (ref "U16") (pin "10") (pinfunction "0P4V_10") (pintype "passive+no_connect"))
    )
    (net (code "57") (name "unconnected-(U16-0P8V-Pad9)") (class "Default")
      (node (ref "U16") (pin "9") (pinfunction "0P8V_9") (pintype "passive+no_connect"))
    )
    (net (code "58") (name "unconnected-(U16-3P2V-Pad6)") (class "Default")
      (node (ref "U16") (pin "6") (pinfunction "3P2V_6") (pintype "passive+no_connect"))
    )
    (net (code "59") (name "unconnected-(U16-6P4V1-Pad5)") (class "Default")
      (node (ref "U16") (pin "5") (pinfunction "6P4V1_5") (pintype "passive+no_connect"))
    )
    (net (code "60") (name "unconnected-(U16-6P4V2-Pad4)") (class "Default")
      (node (ref "U16") (pin "4") (pinfunction "6P4V2_4") (pintype "passive+no_connect"))
    )
    (net (code "61") (name "unconnected-(U16-NC-Pad2)") (class "Default")
      (node (ref "U16") (pin "2") (pinfunction "NC_2") (pintype "passive+no_connect"))
    )
    (net (code "62") (name "unconnected-(U16-NC-Pad17)") (class "Default")
      (node (ref "U16") (pin "17") (pinfunction "NC_17") (pintype "passive+no_connect"))
    )
    (net (code "63") (name "unconnected-(U16-NC-Pad18)") (class "Default")
      (node (ref "U16") (pin "18") (pinfunction "NC_18") (pintype "passive+no_connect"))
    )
    (net (code "64") (name "unconnected-(U16-NC-Pad19)") (class "Default")
      (node (ref "U16") (pin "19") (pinfunction "NC_19") (pintype "passive+no_connect"))
    )
  )
)
